# dcdc.net
KiCad netlist of a schematic drawn in Altium Designer
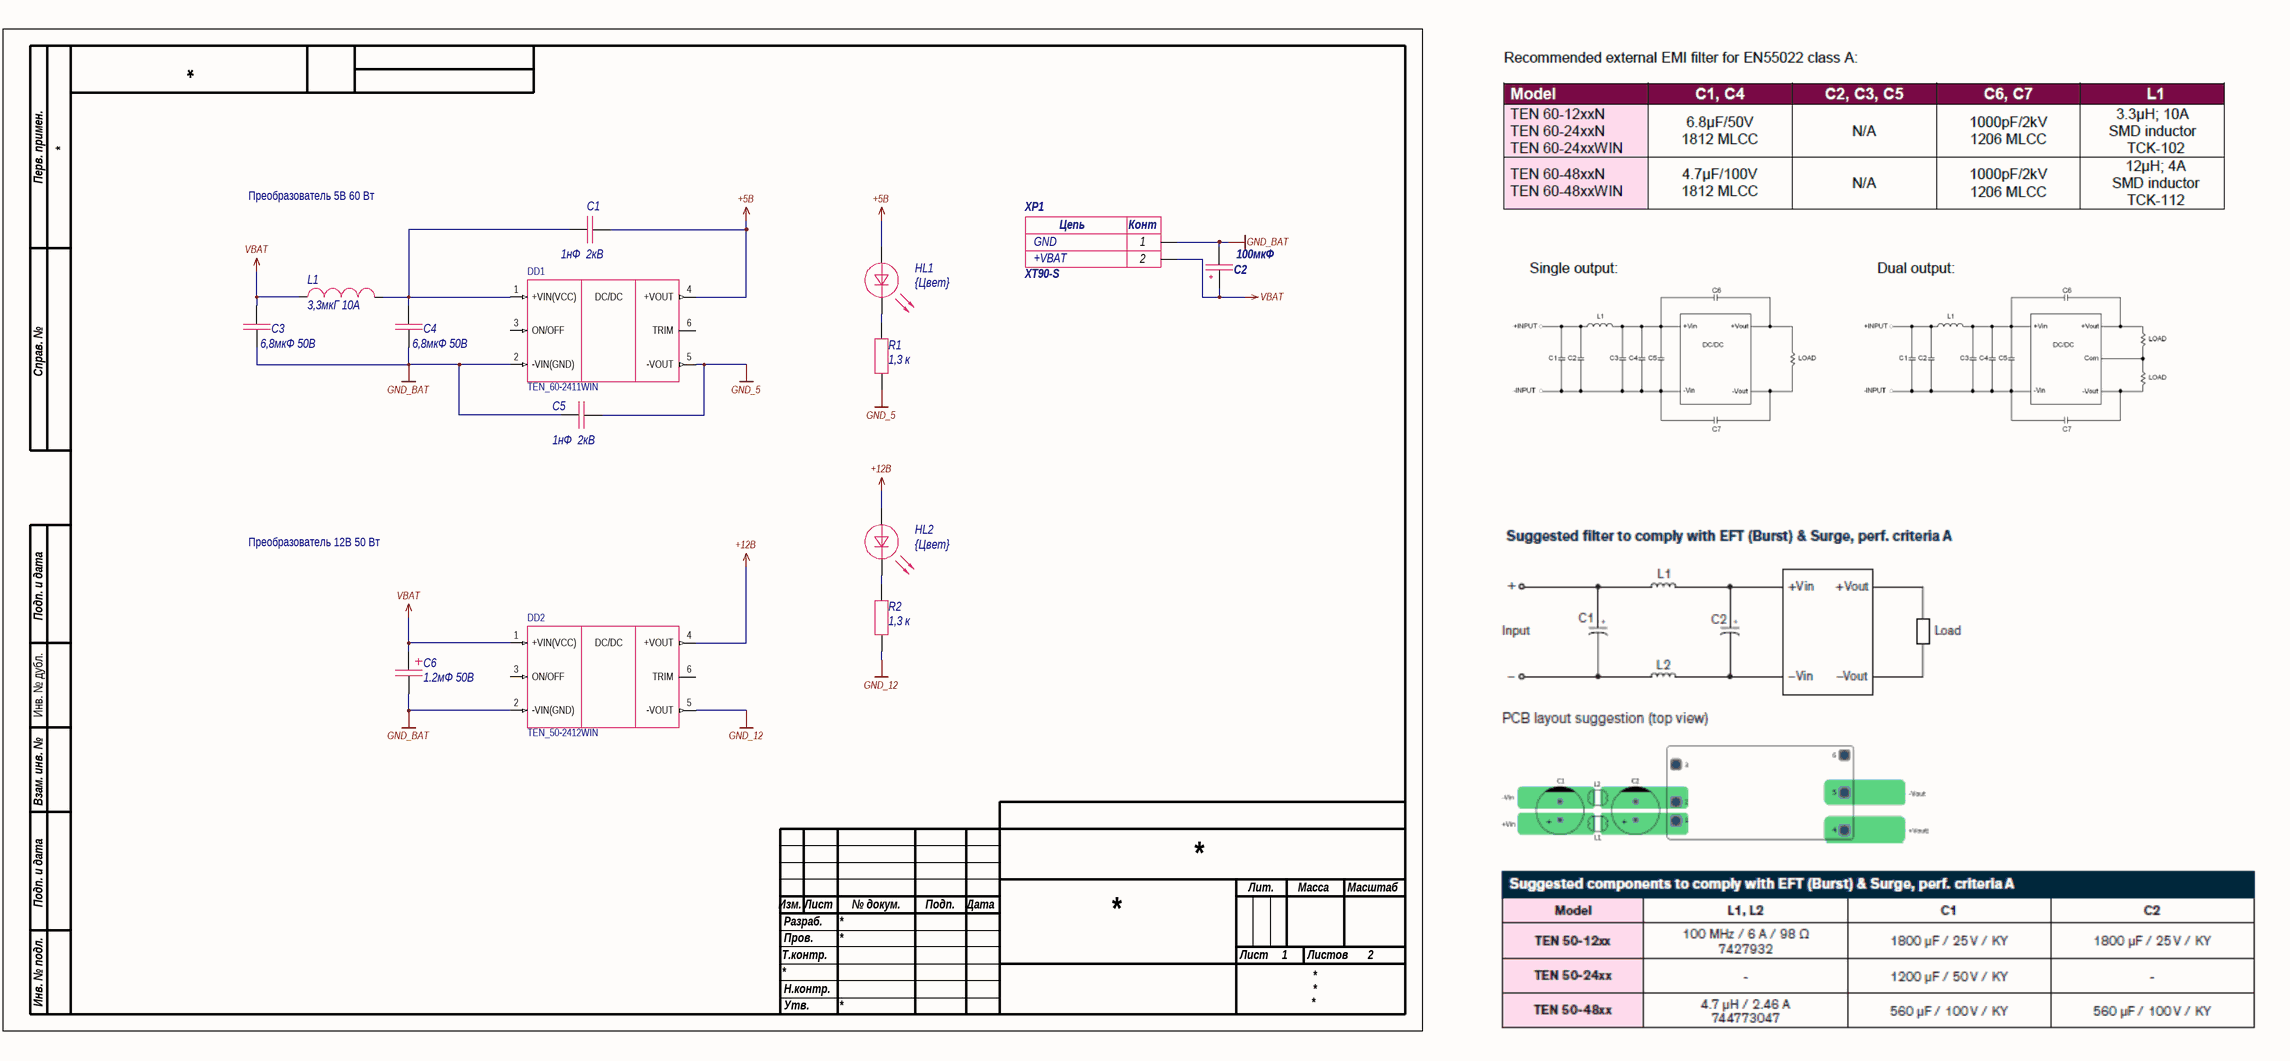
[diagram p0: dcdc.SchDoc]

(export (version "E")
  (design (tool "Eeschema 10.0.6"))
  (components
    (comp (ref "C1")
      (value "1нФ  2кВ")
      (footprint "1206")
      (description "Capacitor")
      (libsource (lib "Hydrolib_sch") (part "Capacitor"))
    )
    (comp (ref "C2")
      (value "100мкФ")
      (footprint "CAPPR65-350-1150X800X1250")
      (fields (field (name "Comment") "100uF"))
      (libsource (lib "MCBoard_sch") (part "Capacitor_pol_100uF"))
    )
    (comp (ref "C3")
      (value "6,8мкФ 50В")
      (footprint "1812")
      (description "Capacitor")
      (libsource (lib "Hydrolib_sch") (part "Capacitor"))
    )
    (comp (ref "C4")
      (value "6,8мкФ 50В")
      (footprint "1812")
      (description "Capacitor")
      (libsource (lib "Hydrolib_sch") (part "Capacitor"))
    )
    (comp (ref "C5")
      (value "1нФ  2кВ")
      (footprint "1206")
      (description "Capacitor")
      (libsource (lib "Hydrolib_sch") (part "Capacitor"))
    )
    (comp (ref "C6")
      (value "1.2мФ 50В")
      (footprint "THD12.5.25")
      (fields (field (name "Comment") "1uF"))
      (libsource (lib "Hydrolib_sch") (part "Capacitor_pol"))
    )
    (comp (ref "DD1")
      (value "TEN_60-2411WIN")
      (footprint "Hydrolib_pcb:CONV_TEN_60-2411WIN")
      (fields (field (name "ALTIUM_VALUE") "DC/DC"))
      (libsource (lib "Hydrolib_sch") (part "TEN_60-2411WIN"))
    )
    (comp (ref "DD2")
      (value "TEN_50-2412WIN")
      (footprint "Hydrolib_pcb:CONV_TEN_60-2411WIN")
      (fields (field (name "MP") "TEN_60-2411WIN") (field (name "ALTIUM_VALUE") "DC/DC"))
      (libsource (lib "Hydrolib_sch") (part "TEN_60-2411WIN"))
    )
    (comp (ref "HL1")
      (value "~")
      (footprint "0805D")
      (fields (field (name "COLOR") "{Цвет}"))
      (libsource (lib "Hydrolib_sch") (part "LED"))
    )
    (comp (ref "HL2")
      (value "~")
      (footprint "0805D")
      (fields (field (name "COLOR") "{Цвет}"))
      (libsource (lib "Hydrolib_sch") (part "LED"))
    )
    (comp (ref "L1")
      (value "3,3мкГ 10А")
      (footprint "TCK-102")
      (fields (field (name "Comment") "Inductance"))
      (libsource (lib "Hydrolib_sch") (part "Inductance"))
    )
    (comp (ref "R1")
      (value "1,3 к")
      (footprint "0603R")
      (fields (field (name "Comment") "Resistor"))
      (libsource (lib "Hydrolib_sch") (part "Resistor"))
    )
    (comp (ref "R2")
      (value "1,3 к")
      (footprint "0603R")
      (fields (field (name "Comment") "Resistor"))
      (libsource (lib "Hydrolib_sch") (part "Resistor"))
    )
    (comp (ref "XP1")
      (value "XT90-S")
      (footprint "AMASS_XT90-M")
      (fields
        (field (name "MANUFACTURER") "Connfly")
        (field (name "VALUE1") "GND")
        (field (name "VALUE2") "+VBAT")
        (field (name "Comment") "XT-90")
      )
      (libsource (lib "Hydrolib_sch") (part "XT-90"))
    )
  )
  (nets
    (net (code "1") (name "+5В") (class "Default")
      (node (ref "C1") (pin "1") (pinfunction "1_1") (pintype "passive"))
      (node (ref "DD1") (pin "4") (pinfunction "+VOUT_4") (pintype "output"))
      (node (ref "HL1") (pin "1") (pinfunction "1_1") (pintype "passive"))
    )
    (net (code "2") (name "+12В") (class "Default")
      (node (ref "DD2") (pin "4") (pinfunction "+VOUT_4") (pintype "output"))
      (node (ref "HL2") (pin "1") (pinfunction "1_1") (pintype "passive"))
    )
    (net (code "3") (name "GND_5") (class "Default")
      (node (ref "C5") (pin "1") (pinfunction "1_1") (pintype "passive"))
      (node (ref "DD1") (pin "5") (pinfunction "-VOUT_5") (pintype "output"))
      (node (ref "R1") (pin "1") (pinfunction "1_1") (pintype "passive"))
    )
    (net (code "4") (name "GND_12") (class "Default")
      (node (ref "DD2") (pin "5") (pinfunction "-VOUT_5") (pintype "output"))
      (node (ref "R2") (pin "1") (pinfunction "1_1") (pintype "passive"))
    )
    (net (code "5") (name "GND_BAT") (class "Default")
      (node (ref "C2") (pin "2") (pinfunction "2_2") (pintype "passive"))
      (node (ref "C3") (pin "1") (pinfunction "1_1") (pintype "passive"))
      (node (ref "C4") (pin "1") (pinfunction "1_1") (pintype "passive"))
      (node (ref "C5") (pin "2") (pinfunction "2_2") (pintype "passive"))
      (node (ref "C6") (pin "2") (pinfunction "2_2") (pintype "passive"))
      (node (ref "DD1") (pin "2") (pinfunction "-VIN(GND)_2") (pintype "input"))
      (node (ref "DD2") (pin "2") (pinfunction "-VIN(GND)_2") (pintype "input"))
      (node (ref "XP1") (pin "1") (pinfunction "1_1") (pintype "passive"))
    )
    (net (code "6") (name "Net-(DD1-+VIN(VCC))") (class "Default")
      (node (ref "C1") (pin "2") (pinfunction "2_2") (pintype "passive"))
      (node (ref "C4") (pin "2") (pinfunction "2_2") (pintype "passive"))
      (node (ref "DD1") (pin "1") (pinfunction "+VIN(VCC)_1") (pintype "input"))
      (node (ref "L1") (pin "2") (pinfunction "2_2") (pintype "passive"))
    )
    (net (code "7") (name "Net-(HL1-Pad2)") (class "Default")
      (node (ref "HL1") (pin "2") (pinfunction "2_2") (pintype "passive"))
      (node (ref "R1") (pin "2") (pinfunction "2_2") (pintype "passive"))
    )
    (net (code "8") (name "Net-(HL2-Pad2)") (class "Default")
      (node (ref "HL2") (pin "2") (pinfunction "2_2") (pintype "passive"))
      (node (ref "R2") (pin "2") (pinfunction "2_2") (pintype "passive"))
    )
    (net (code "9") (name "VBAT") (class "Default")
      (node (ref "C2") (pin "1") (pinfunction "1_1") (pintype "passive"))
      (node (ref "C3") (pin "2") (pinfunction "2_2") (pintype "passive"))
      (node (ref "C6") (pin "1") (pinfunction "1_1") (pintype "passive"))
      (node (ref "DD2") (pin "1") (pinfunction "+VIN(VCC)_1") (pintype "input"))
      (node (ref "L1") (pin "1") (pinfunction "1_1") (pintype "passive"))
      (node (ref "XP1") (pin "2") (pinfunction "2_2") (pintype "passive"))
    )
    (net (code "10") (name "unconnected-(DD1-ON{slash}OFF-Pad3)") (class "Default")
      (node (ref "DD1") (pin "3") (pinfunction "ON/OFF_3") (pintype "input"))
    )
    (net (code "11") (name "unconnected-(DD1-TRIM-Pad6)") (class "Default")
      (node (ref "DD1") (pin "6") (pinfunction "TRIM_6") (pintype "passive"))
    )
    (net (code "12") (name "unconnected-(DD2-ON{slash}OFF-Pad3)") (class "Default")
      (node (ref "DD2") (pin "3") (pinfunction "ON/OFF_3") (pintype "input"))
    )
    (net (code "13") (name "unconnected-(DD2-TRIM-Pad6)") (class "Default")
      (node (ref "DD2") (pin "6") (pinfunction "TRIM_6") (pintype "passive"))
    )
  )
)
